# EPS_Distribution_Measurements.net
KiCad netlist of a schematic drawn in Altium Designer
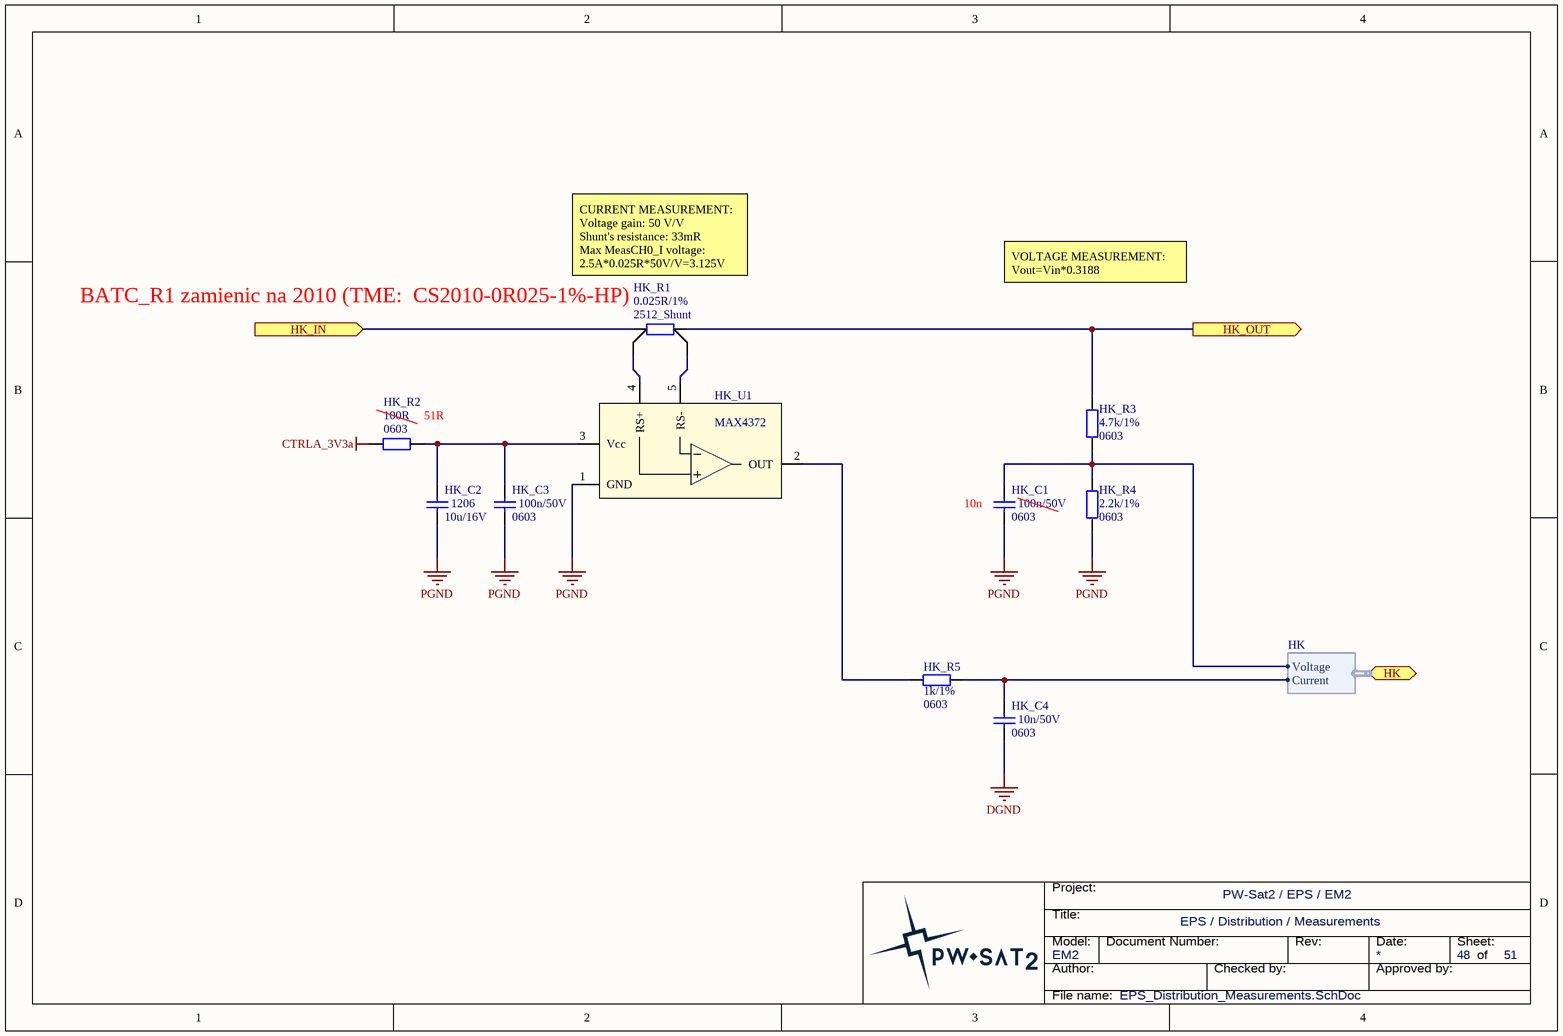
[diagram p0: EPS_Distribution_Measurements.SchDoc]

(export (version "E")
  (design (tool "Eeschema 10.0.6"))
  (components
    (comp (ref "HK_C1")
      (value "100n/50V")
      (footprint "SMD_Capacitor_0603")
      (description "Ceramic Cap Kemet COTS 100n/50V X7R 0603")
      (fields
        (field (name "MANUFACTURER") "Kemet")
        (field (name "MANUFACTURERPARTNUMBER") "C0603T104K5RALTU")
        (field (name "PACKAGE") "0603")
      )
      (libsource (lib "capacitors") (part "Cer_C0603T104K5RALTU"))
    )
    (comp (ref "HK_C2")
      (value "10u/16V")
      (footprint "SMD_Capacitor_1206")
      (description "Ceramic Cap Kemet COTS 10u/16V X7R 1206")
      (fields
        (field (name "MANUFACTURERPARTNUMBER") "C1206T106K4RACTU")
        (field (name "MANUFACTURER") "Kemet")
        (field (name "PACKGE") "1206")
      )
      (libsource (lib "capacitors") (part "Cer_C1206T106K4RACTU"))
    )
    (comp (ref "HK_C3")
      (value "100n/50V")
      (footprint "SMD_Capacitor_0603")
      (description "Ceramic Cap Kemet COTS 100n/50V X7R 0603")
      (fields
        (field (name "MANUFACTURER") "Kemet")
        (field (name "MANUFACTURERPARTNUMBER") "C0603T104K5RALTU")
        (field (name "PACKAGE") "0603")
      )
      (libsource (lib "capacitors") (part "Cer_C0603T104K5RALTU"))
    )
    (comp (ref "HK_C4")
      (value "10n/50V")
      (footprint "SMD_Capacitor_0603")
      (description "Ceramic Cap Kemet COTS 100n/50V X7R 0603")
      (fields
        (field (name "MANUFACTURER") "Kemet")
        (field (name "MANUFACTURERPARTNUMBER") "C0603T104K5RALTU")
        (field (name "PACKAGE") "0603")
      )
      (libsource (lib "capacitors") (part "Cer_C0603T104K5RALTU"))
    )
    (comp (ref "HK_R1")
      (value "0.025R/1%")
      (footprint "SMD_Resistor-shunt_2512")
      (description "33mR ,1%, 2W, shunt resistor, TE Connectivity.")
      (fields
        (field (name "MANUFACTURERPARTNUMBER") "LR2512-R033FW")
        (field (name "MANUFACTURER") "TE Connectivity")
        (field (name "PACKAGE") "2512_Shunt")
      )
      (libsource (lib "resistors") (part "LR2512-R033FW"))
    )
    (comp (ref "HK_R2")
      (value "100R")
      (footprint "SMD_Resistor_0603")
      (fields (field (name "PACKAGE") "0603"))
      (libsource (lib "") (part "Res_1"))
    )
    (comp (ref "HK_R3")
      (value "4.7k/1%")
      (footprint "SMD_Resistor_0603")
      (fields (field (name "PACKAGE") "0603"))
      (libsource (lib "resistors") (part "Res"))
    )
    (comp (ref "HK_R4")
      (value "2.2k/1%")
      (footprint "SMD_Resistor_0603")
      (fields (field (name "PACKAGE") "0603"))
      (libsource (lib "resistors") (part "Res"))
    )
    (comp (ref "HK_R5")
      (value "1k/1%")
      (footprint "SMD_Resistor_0603")
      (fields (field (name "PACKAGE") "0603"))
      (libsource (lib "") (part "Res_1"))
    )
    (comp (ref "HK_U1")
      (value "MAX4372")
      (footprint "SOT23-5")
      (description "High-Side Current-Sense Amplifier with Voltage Output")
      (fields (field (name "MANUFACTURER") "Maxim Integrated Products"))
      (libsource (lib "microcircuits") (part "MAX4372"))
    )
  )
  (nets
    (net (code "2") (name "/HK_IN") (class "Default")
      (node (ref "HK_R1") (pin "1") (pinfunction "1_1") (pintype "passive"))
    )
    (net (code "3") (name "/HK_OUT") (class "Default")
      (node (ref "HK_R1") (pin "4") (pinfunction "4_4") (pintype "passive"))
      (node (ref "HK_R3") (pin "1") (pinfunction "1_1") (pintype "passive"))
    )
    (net (code "5") (name "CTRLA_3V3a") (class "Default")
      (node (ref "HK_R2") (pin "1") (pinfunction "1_1") (pintype "passive"))
    )
    (net (code "6") (name "DGND") (class "Default")
      (node (ref "HK_C4") (pin "2") (pinfunction "2_2") (pintype "passive"))
    )
    (net (code "7") (name "Net-(HK_C1-Pad1)") (class "Default")
      (node (ref "HK_C1") (pin "1") (pinfunction "1_1") (pintype "passive"))
      (node (ref "HK_R3") (pin "2") (pinfunction "2_2") (pintype "passive"))
      (node (ref "HK_R4") (pin "1") (pinfunction "1_1") (pintype "passive"))
    )
    (net (code "8") (name "Net-(HK_C4-Pad1)") (class "Default")
      (node (ref "HK_C4") (pin "1") (pinfunction "1_1") (pintype "passive"))
      (node (ref "HK_R5") (pin "2") (pinfunction "2_2") (pintype "passive"))
    )
    (net (code "9") (name "Net-(HK_U1-OUT)") (class "Default")
      (node (ref "HK_R5") (pin "1") (pinfunction "1_1") (pintype "passive"))
      (node (ref "HK_U1") (pin "2") (pinfunction "OUT_2") (pintype "passive"))
    )
    (net (code "10") (name "Net-(HK_U1-RS+)") (class "Default")
      (node (ref "HK_R1") (pin "2") (pinfunction "2_2") (pintype "passive"))
      (node (ref "HK_U1") (pin "4") (pinfunction "RS+_4") (pintype "passive"))
    )
    (net (code "11") (name "Net-(HK_U1-RS-)") (class "Default")
      (node (ref "HK_R1") (pin "3") (pinfunction "3_3") (pintype "passive"))
      (node (ref "HK_U1") (pin "5") (pinfunction "RS-_5") (pintype "passive"))
    )
    (net (code "12") (name "Net-(HK_U1-Vcc)") (class "Default")
      (node (ref "HK_C2") (pin "1") (pinfunction "1_1") (pintype "passive"))
      (node (ref "HK_C3") (pin "1") (pinfunction "1_1") (pintype "passive"))
      (node (ref "HK_R2") (pin "2") (pinfunction "2_2") (pintype "passive"))
      (node (ref "HK_U1") (pin "3") (pinfunction "Vcc_3") (pintype "passive"))
    )
    (net (code "13") (name "PGND") (class "Default")
      (node (ref "HK_C1") (pin "2") (pinfunction "2_2") (pintype "passive"))
      (node (ref "HK_C2") (pin "2") (pinfunction "2_2") (pintype "passive"))
      (node (ref "HK_C3") (pin "2") (pinfunction "2_2") (pintype "passive"))
      (node (ref "HK_R4") (pin "2") (pinfunction "2_2") (pintype "passive"))
      (node (ref "HK_U1") (pin "1") (pinfunction "GND_1") (pintype "passive"))
    )
  )
)
